# blimp_v2.net
KiCad netlist of a schematic drawn in EAGLE
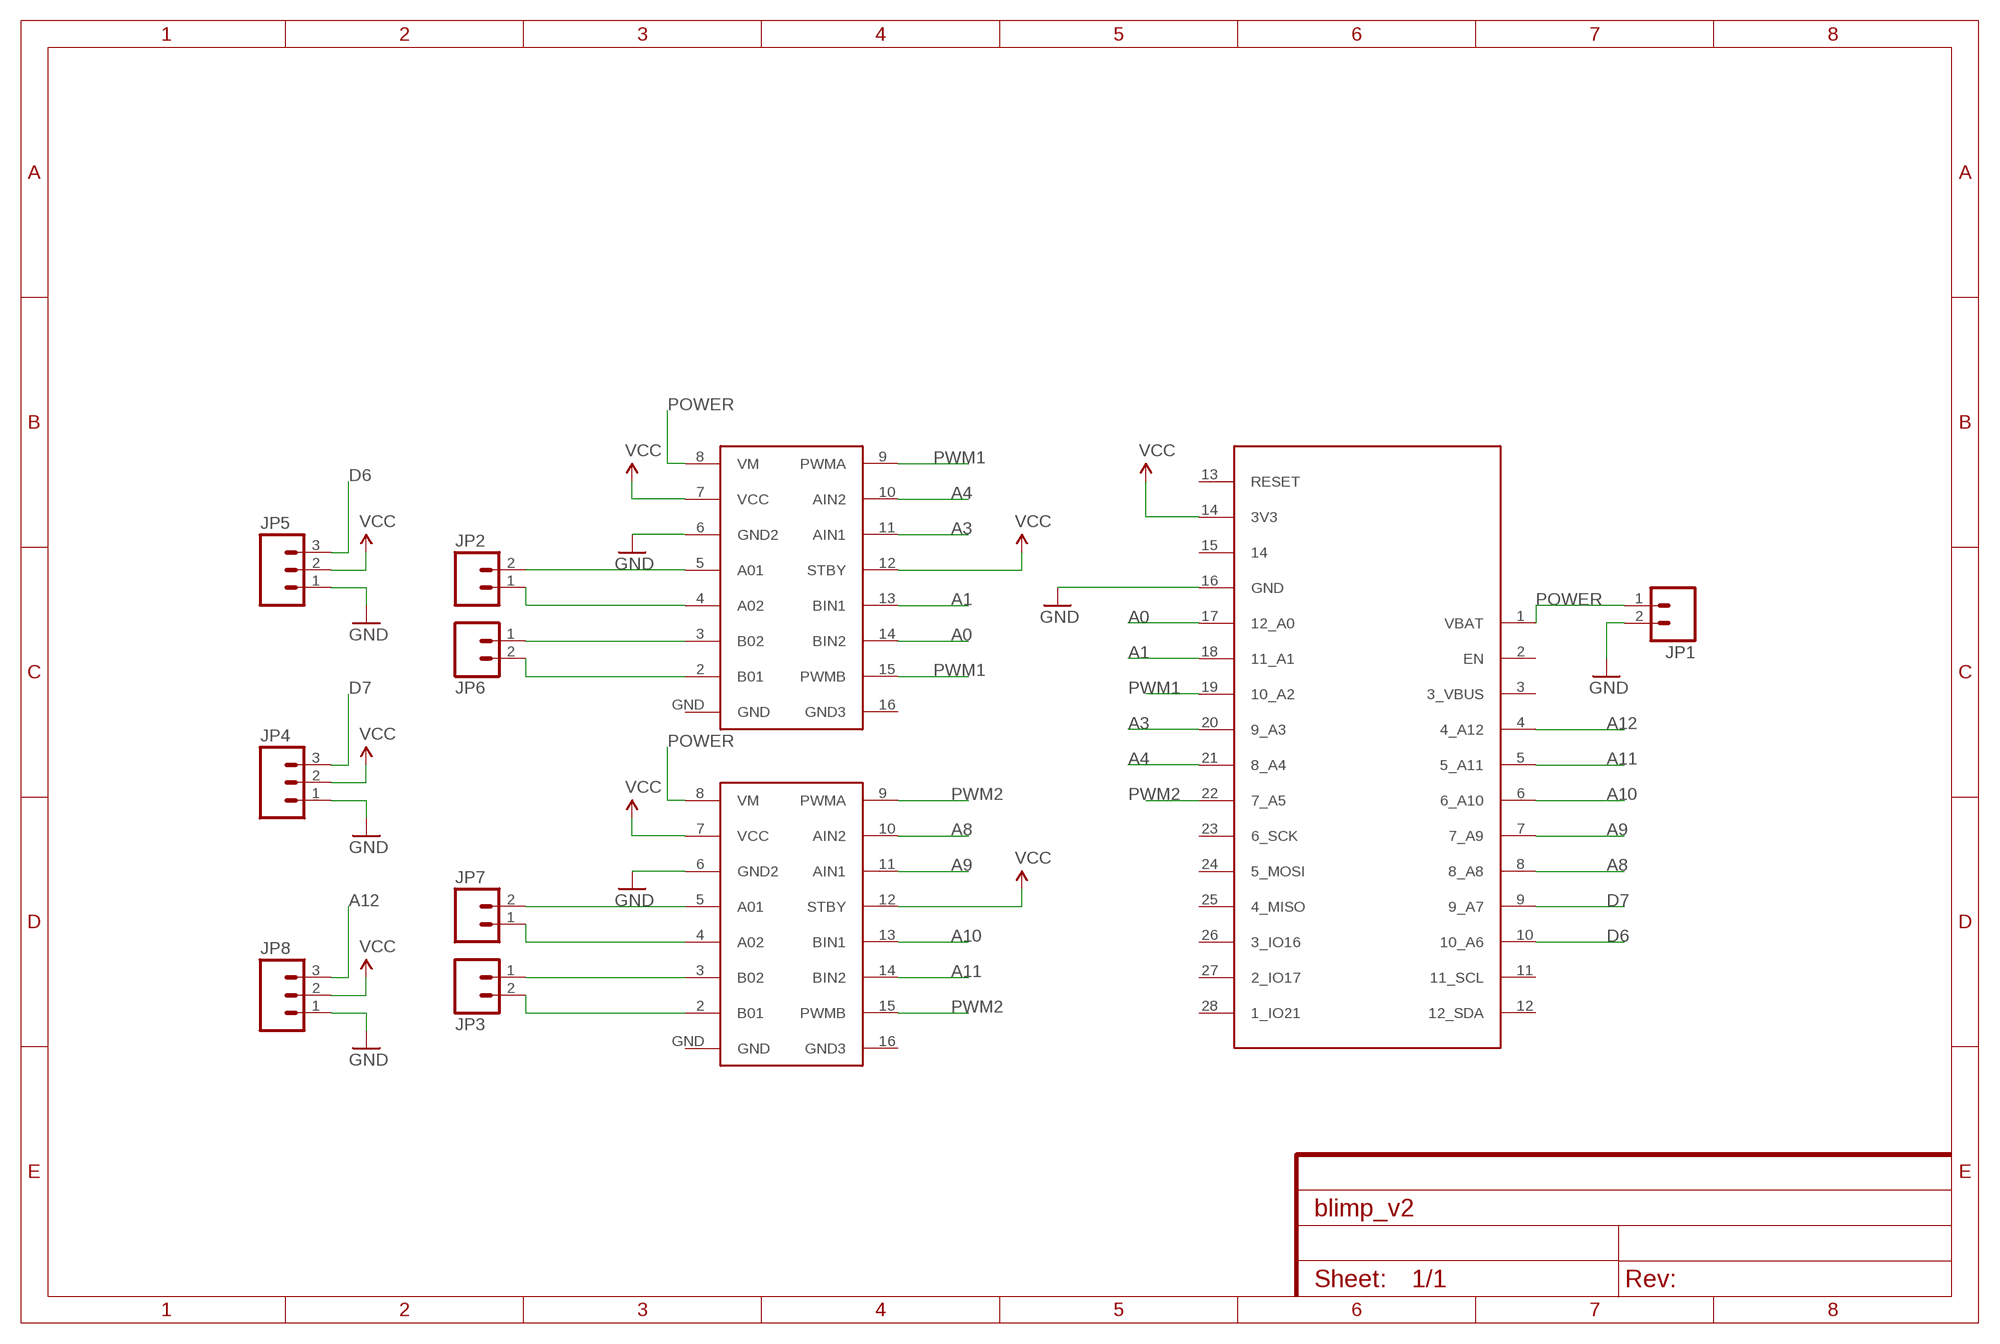
[diagram p0: schematic, sheet 1]

(export (version "E")
  (design (tool "Eeschema 10.0.6"))
  (components
    (comp (ref "JP1")
      (value "M02-JST-2MM-SMT")
      (footprint "eagle-import:JST-2-SMD")
      (libsource (lib "eagle-import") (part "M02-JST-2MM-SMT"))
    )
    (comp (ref "JP2")
      (value "M02PTH")
      (footprint "eagle-import:1X02")
      (libsource (lib "eagle-import") (part "M02PTH"))
    )
    (comp (ref "JP3")
      (value "M02PTH")
      (footprint "eagle-import:1X02")
      (libsource (lib "eagle-import") (part "M02PTH"))
    )
    (comp (ref "JP4")
      (value "M03PTH")
      (footprint "eagle-import:1X03")
      (libsource (lib "eagle-import") (part "M03PTH"))
    )
    (comp (ref "JP5")
      (value "M03PTH")
      (footprint "eagle-import:1X03")
      (libsource (lib "eagle-import") (part "M03PTH"))
    )
    (comp (ref "JP6")
      (value "M02PTH")
      (footprint "eagle-import:1X02")
      (libsource (lib "eagle-import") (part "M02PTH"))
    )
    (comp (ref "JP7")
      (value "M02PTH")
      (footprint "eagle-import:1X02")
      (libsource (lib "eagle-import") (part "M02PTH"))
    )
    (comp (ref "JP8")
      (value "M03PTH")
      (footprint "eagle-import:1X03")
      (libsource (lib "eagle-import") (part "M03PTH"))
    )
    (comp (ref "U$1")
      (value "ESP32")
      (footprint "eagle-import:ESP32")
      (libsource (lib "eagle-import") (part "ESP32"))
    )
    (comp (ref "U$2")
      (value "TB6612")
      (footprint "eagle-import:TB6612")
      (libsource (lib "eagle-import") (part "TB6612"))
    )
    (comp (ref "U$4")
      (value "TB6612")
      (footprint "eagle-import:TB6612")
      (libsource (lib "eagle-import") (part "TB6612"))
    )
  )
  (nets
    (net (code "1") (name "/A0") (class "Default")
      (node (ref "U$1") (pin "17") (pinfunction "12_A0_17") (pintype "bidirectional"))
      (node (ref "U$4") (pin "14") (pinfunction "BIN2_14") (pintype "bidirectional"))
    )
    (net (code "2") (name "/A1") (class "Default")
      (node (ref "U$1") (pin "18") (pinfunction "11_A1_18") (pintype "bidirectional"))
      (node (ref "U$4") (pin "13") (pinfunction "BIN1_13") (pintype "bidirectional"))
    )
    (net (code "3") (name "/A3") (class "Default")
      (node (ref "U$1") (pin "20") (pinfunction "9_A3_20") (pintype "bidirectional"))
      (node (ref "U$4") (pin "11") (pinfunction "AIN1_11") (pintype "bidirectional"))
    )
    (net (code "4") (name "/A4") (class "Default")
      (node (ref "U$1") (pin "21") (pinfunction "8_A4_21") (pintype "bidirectional"))
      (node (ref "U$4") (pin "10") (pinfunction "AIN2_10") (pintype "bidirectional"))
    )
    (net (code "5") (name "/A8") (class "Default")
      (node (ref "U$1") (pin "8") (pinfunction "8_A8_8") (pintype "bidirectional"))
      (node (ref "U$2") (pin "10") (pinfunction "AIN2_10") (pintype "bidirectional"))
    )
    (net (code "6") (name "/A9") (class "Default")
      (node (ref "U$1") (pin "7") (pinfunction "7_A9_7") (pintype "bidirectional"))
      (node (ref "U$2") (pin "11") (pinfunction "AIN1_11") (pintype "bidirectional"))
    )
    (net (code "7") (name "/A10") (class "Default")
      (node (ref "U$1") (pin "6") (pinfunction "6_A10_6") (pintype "bidirectional"))
      (node (ref "U$2") (pin "13") (pinfunction "BIN1_13") (pintype "bidirectional"))
    )
    (net (code "8") (name "/A11") (class "Default")
      (node (ref "U$1") (pin "5") (pinfunction "5_A11_5") (pintype "bidirectional"))
      (node (ref "U$2") (pin "14") (pinfunction "BIN2_14") (pintype "bidirectional"))
    )
    (net (code "9") (name "/A12") (class "Default")
      (node (ref "JP8") (pin "3") (pinfunction "3_3") (pintype "passive"))
      (node (ref "U$1") (pin "4") (pinfunction "4_A12_4") (pintype "bidirectional"))
    )
    (net (code "10") (name "/D6") (class "Default")
      (node (ref "JP5") (pin "3") (pinfunction "3_3") (pintype "passive"))
      (node (ref "U$1") (pin "10") (pinfunction "10_A6_10") (pintype "bidirectional"))
    )
    (net (code "11") (name "/D7") (class "Default")
      (node (ref "JP4") (pin "3") (pinfunction "3_3") (pintype "passive"))
      (node (ref "U$1") (pin "9") (pinfunction "9_A7_9") (pintype "bidirectional"))
    )
    (net (code "12") (name "/POWER") (class "Default")
      (node (ref "JP1") (pin "1") (pinfunction "1_1") (pintype "passive"))
      (node (ref "U$1") (pin "1") (pinfunction "VBAT_1") (pintype "bidirectional"))
      (node (ref "U$2") (pin "8") (pinfunction "VM_8") (pintype "bidirectional"))
      (node (ref "U$4") (pin "8") (pinfunction "VM_8") (pintype "bidirectional"))
    )
    (net (code "13") (name "/PWM1") (class "Default")
      (node (ref "U$1") (pin "19") (pinfunction "10_A2_19") (pintype "bidirectional"))
      (node (ref "U$4") (pin "15") (pinfunction "PWMB_15") (pintype "bidirectional"))
      (node (ref "U$4") (pin "9") (pinfunction "PWMA_9") (pintype "bidirectional"))
    )
    (net (code "14") (name "/PWM2") (class "Default")
      (node (ref "U$1") (pin "22") (pinfunction "7_A5_22") (pintype "bidirectional"))
      (node (ref "U$2") (pin "15") (pinfunction "PWMB_15") (pintype "bidirectional"))
      (node (ref "U$2") (pin "9") (pinfunction "PWMA_9") (pintype "bidirectional"))
    )
    (net (code "15") (name "GND") (class "Default")
      (node (ref "JP1") (pin "2") (pinfunction "2_2") (pintype "passive"))
      (node (ref "JP4") (pin "1") (pinfunction "1_1") (pintype "passive"))
      (node (ref "JP5") (pin "1") (pinfunction "1_1") (pintype "passive"))
      (node (ref "JP8") (pin "1") (pinfunction "1_1") (pintype "passive"))
      (node (ref "U$1") (pin "16") (pinfunction "GND_16") (pintype "bidirectional"))
      (node (ref "U$2") (pin "6") (pinfunction "GND2_6") (pintype "bidirectional"))
      (node (ref "U$4") (pin "6") (pinfunction "GND2_6") (pintype "bidirectional"))
    )
    (net (code "16") (name "Net-(U$2-A01)") (class "Default")
      (node (ref "JP7") (pin "2") (pinfunction "2_2") (pintype "passive"))
      (node (ref "U$2") (pin "5") (pinfunction "A01_5") (pintype "bidirectional"))
    )
    (net (code "17") (name "Net-(U$2-A02)") (class "Default")
      (node (ref "JP7") (pin "1") (pinfunction "1_1") (pintype "passive"))
      (node (ref "U$2") (pin "4") (pinfunction "A02_4") (pintype "bidirectional"))
    )
    (net (code "18") (name "Net-(U$2-B01)") (class "Default")
      (node (ref "JP3") (pin "2") (pinfunction "2_2") (pintype "passive"))
      (node (ref "U$2") (pin "2") (pinfunction "B01_2") (pintype "bidirectional"))
    )
    (net (code "19") (name "Net-(U$2-B02)") (class "Default")
      (node (ref "JP3") (pin "1") (pinfunction "1_1") (pintype "passive"))
      (node (ref "U$2") (pin "3") (pinfunction "B02_3") (pintype "bidirectional"))
    )
    (net (code "20") (name "Net-(U$4-A01)") (class "Default")
      (node (ref "JP2") (pin "2") (pinfunction "2_2") (pintype "passive"))
      (node (ref "U$4") (pin "5") (pinfunction "A01_5") (pintype "bidirectional"))
    )
    (net (code "21") (name "Net-(U$4-A02)") (class "Default")
      (node (ref "JP2") (pin "1") (pinfunction "1_1") (pintype "passive"))
      (node (ref "U$4") (pin "4") (pinfunction "A02_4") (pintype "bidirectional"))
    )
    (net (code "22") (name "Net-(U$4-B01)") (class "Default")
      (node (ref "JP6") (pin "2") (pinfunction "2_2") (pintype "passive"))
      (node (ref "U$4") (pin "2") (pinfunction "B01_2") (pintype "bidirectional"))
    )
    (net (code "23") (name "Net-(U$4-B02)") (class "Default")
      (node (ref "JP6") (pin "1") (pinfunction "1_1") (pintype "passive"))
      (node (ref "U$4") (pin "3") (pinfunction "B02_3") (pintype "bidirectional"))
    )
    (net (code "24") (name "VCC") (class "Default")
      (node (ref "JP4") (pin "2") (pinfunction "2_2") (pintype "passive"))
      (node (ref "JP5") (pin "2") (pinfunction "2_2") (pintype "passive"))
      (node (ref "JP8") (pin "2") (pinfunction "2_2") (pintype "passive"))
      (node (ref "U$1") (pin "14") (pinfunction "3V3_14") (pintype "bidirectional"))
      (node (ref "U$2") (pin "12") (pinfunction "STBY_12") (pintype "bidirectional"))
      (node (ref "U$2") (pin "7") (pinfunction "VCC_7") (pintype "bidirectional"))
      (node (ref "U$4") (pin "12") (pinfunction "STBY_12") (pintype "bidirectional"))
      (node (ref "U$4") (pin "7") (pinfunction "VCC_7") (pintype "bidirectional"))
    )
    (net (code "25") (name "unconnected-(U$1-1_IO21-Pad28)") (class "Default")
      (node (ref "U$1") (pin "28") (pinfunction "1_IO21_28") (pintype "bidirectional"))
    )
    (net (code "26") (name "unconnected-(U$1-2_IO17-Pad27)") (class "Default")
      (node (ref "U$1") (pin "27") (pinfunction "2_IO17_27") (pintype "bidirectional"))
    )
    (net (code "27") (name "unconnected-(U$1-3_IO16-Pad26)") (class "Default")
      (node (ref "U$1") (pin "26") (pinfunction "3_IO16_26") (pintype "bidirectional"))
    )
    (net (code "28") (name "unconnected-(U$1-3_VBUS-Pad3)") (class "Default")
      (node (ref "U$1") (pin "3") (pinfunction "3_VBUS_3") (pintype "bidirectional"))
    )
    (net (code "29") (name "unconnected-(U$1-4_MISO-Pad25)") (class "Default")
      (node (ref "U$1") (pin "25") (pinfunction "4_MISO_25") (pintype "bidirectional"))
    )
    (net (code "30") (name "unconnected-(U$1-5_MOSI-Pad24)") (class "Default")
      (node (ref "U$1") (pin "24") (pinfunction "5_MOSI_24") (pintype "bidirectional"))
    )
    (net (code "31") (name "unconnected-(U$1-6_SCK-Pad23)") (class "Default")
      (node (ref "U$1") (pin "23") (pinfunction "6_SCK_23") (pintype "bidirectional"))
    )
    (net (code "32") (name "unconnected-(U$1-11_SCL-Pad11)") (class "Default")
      (node (ref "U$1") (pin "11") (pinfunction "11_SCL_11") (pintype "bidirectional"))
    )
    (net (code "33") (name "unconnected-(U$1-12_SDA-Pad12)") (class "Default")
      (node (ref "U$1") (pin "12") (pinfunction "12_SDA_12") (pintype "bidirectional"))
    )
    (net (code "34") (name "unconnected-(U$1-14-Pad15)") (class "Default")
      (node (ref "U$1") (pin "15") (pinfunction "14_15") (pintype "bidirectional"))
    )
    (net (code "35") (name "unconnected-(U$1-EN-Pad2)") (class "Default")
      (node (ref "U$1") (pin "2") (pinfunction "EN_2") (pintype "bidirectional"))
    )
    (net (code "36") (name "unconnected-(U$1-RESET-Pad13)") (class "Default")
      (node (ref "U$1") (pin "13") (pinfunction "RESET_13") (pintype "bidirectional"))
    )
    (net (code "37") (name "unconnected-(U$2-GND3-Pad16)") (class "Default")
      (node (ref "U$2") (pin "16") (pinfunction "GND3_16") (pintype "bidirectional"))
    )
    (net (code "38") (name "unconnected-(U$2-PadGND)") (class "Default")
      (node (ref "U$2") (pin "GND") (pinfunction "GND_GND") (pintype "bidirectional"))
    )
    (net (code "39") (name "unconnected-(U$4-GND3-Pad16)") (class "Default")
      (node (ref "U$4") (pin "16") (pinfunction "GND3_16") (pintype "bidirectional"))
    )
    (net (code "40") (name "unconnected-(U$4-PadGND)") (class "Default")
      (node (ref "U$4") (pin "GND") (pinfunction "GND_GND") (pintype "bidirectional"))
    )
  )
)
